# 03_CONNECTOR.net
KiCad netlist of a schematic drawn in Altium Designer
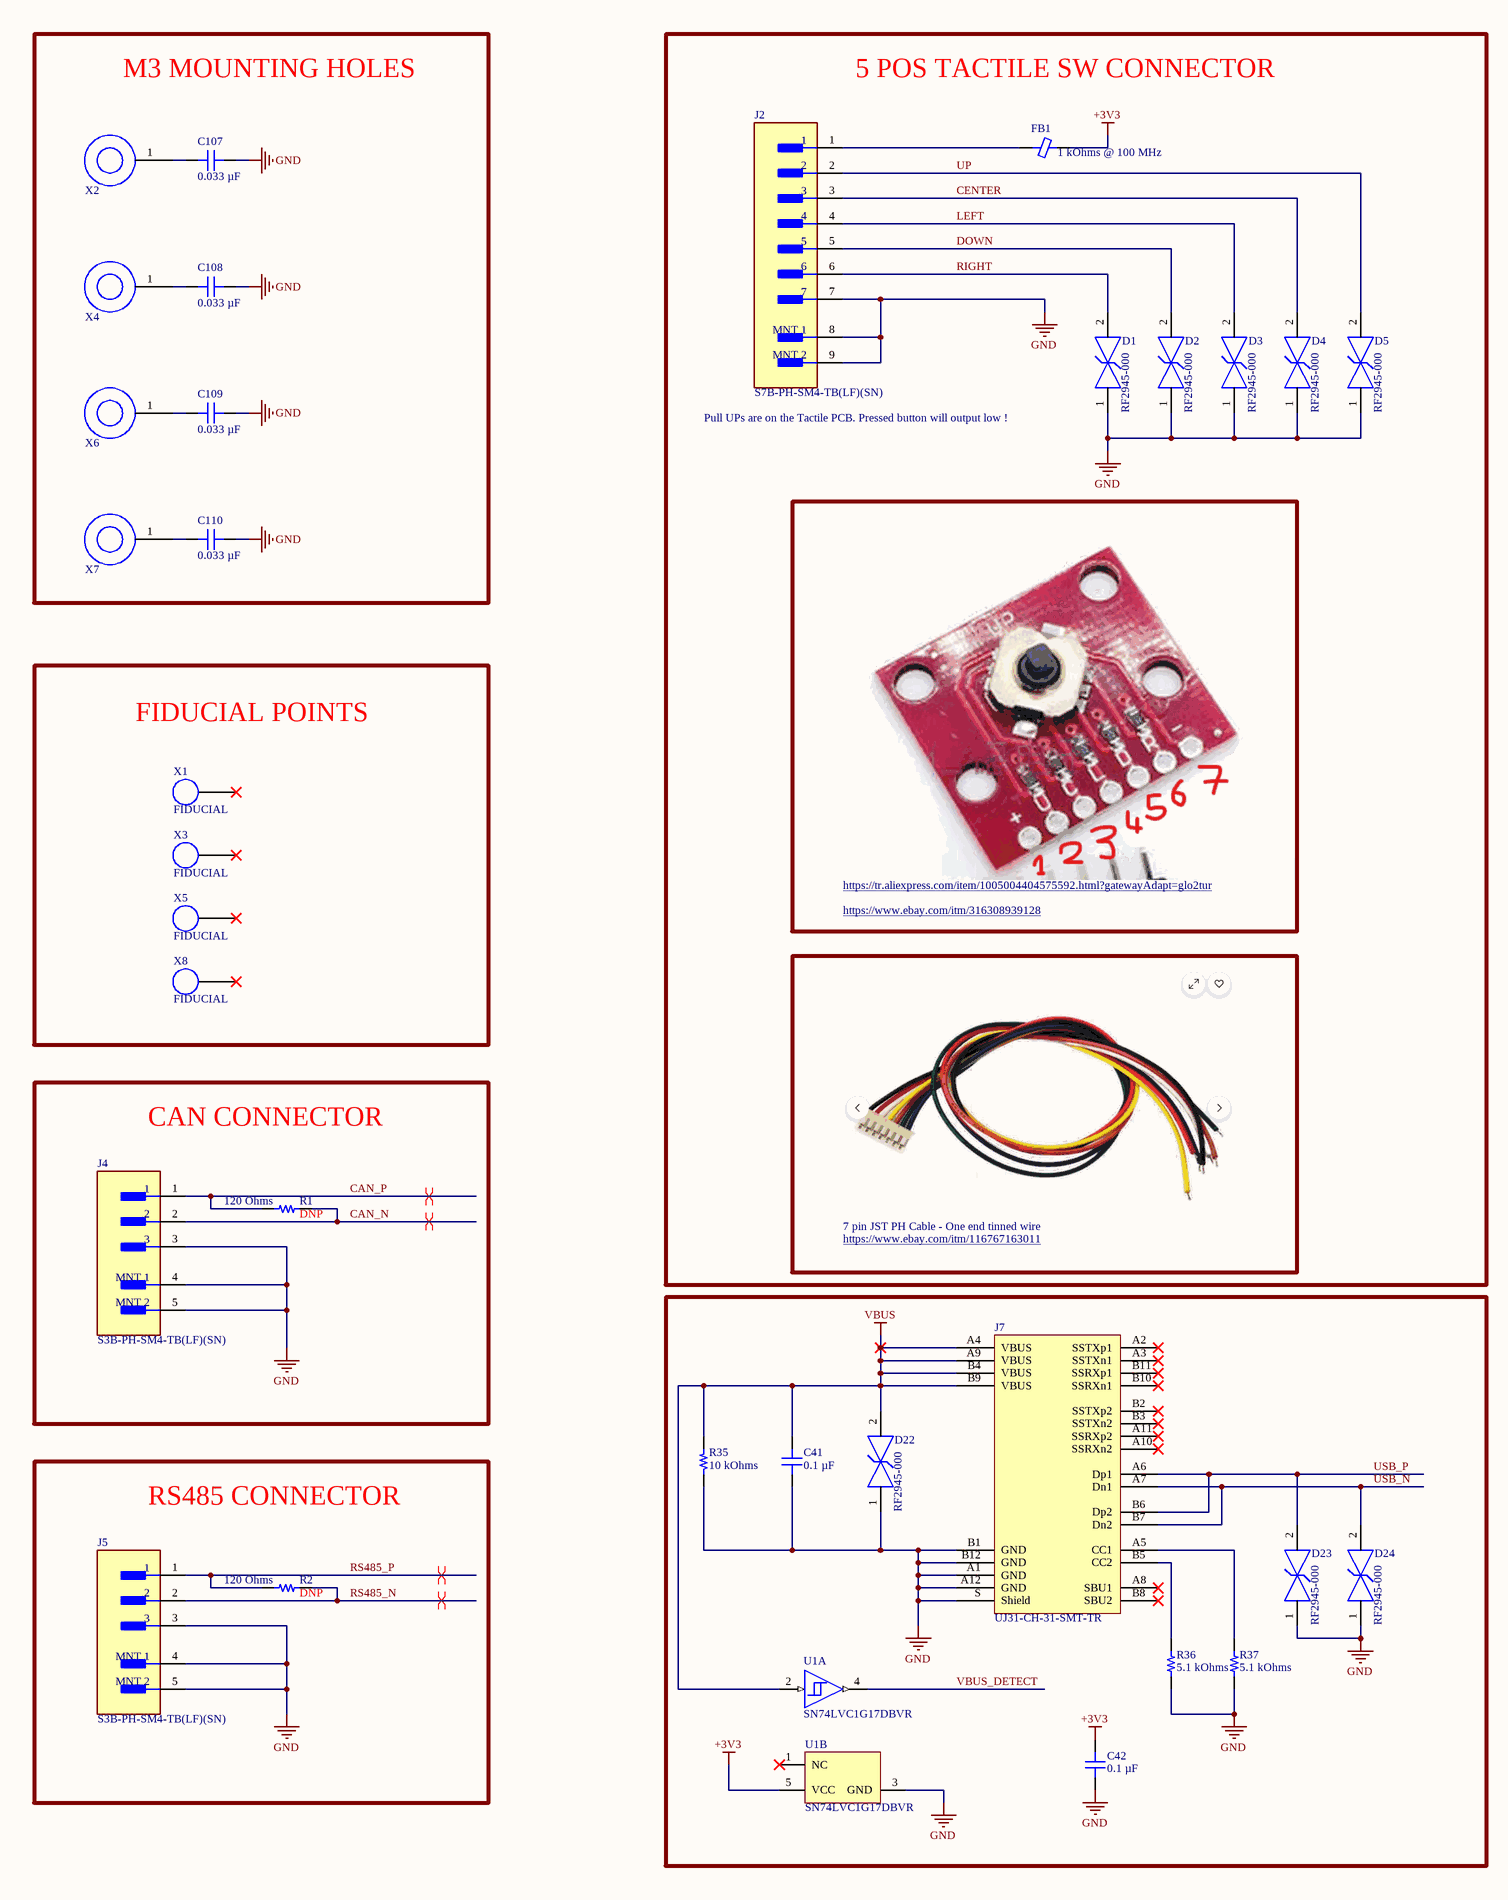
[diagram p0: 03_CONNECTOR.SchDoc, left]
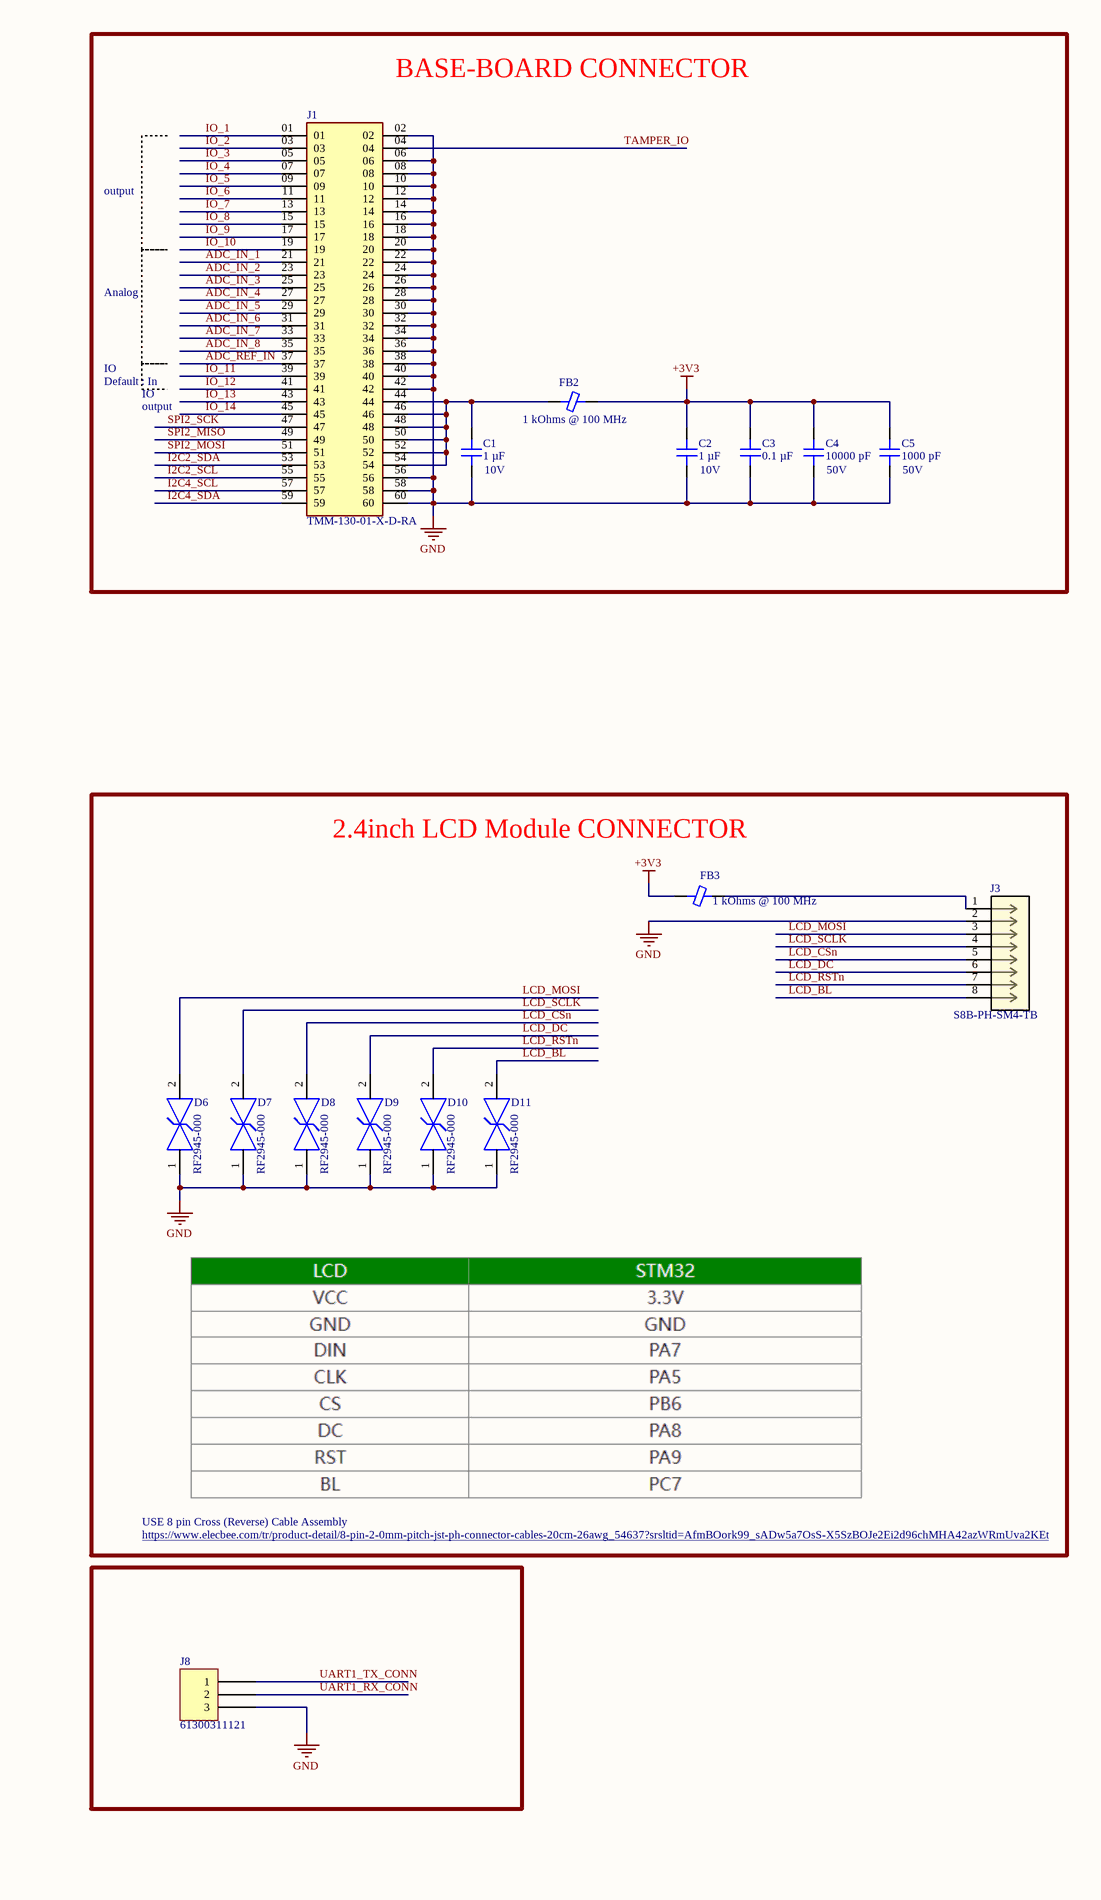
[diagram p1: 03_CONNECTOR.SchDoc, right]

(export (version "E")
  (design (tool "Eeschema 10.0.6"))
  (components
    (comp (ref "C1")
      (value "1 µF")
      (footprint "CAP 0402_1005")
      (description "CAP CER 1UF 10V X7S 0402")
      (fields
        (field (name "PART NUMBER") "C1005X7S1A105K050BC")
        (field (name "MANUFACTURER") "TDK Corporation")
        (field (name "VOLTAGE - RATED") "10V")
      )
      (libsource (lib "Celestial Altium Library - altium_library") (part "Capacitor"))
    )
    (comp (ref "C2")
      (value "1 µF")
      (footprint "CAP 0402_1005")
      (description "CAP CER 1UF 10V X7S 0402")
      (fields
        (field (name "PART NUMBER") "C1005X7S1A105K050BC")
        (field (name "MANUFACTURER") "TDK Corporation")
        (field (name "VOLTAGE - RATED") "10V")
      )
      (libsource (lib "Celestial Altium Library - altium_library") (part "Capacitor"))
    )
    (comp (ref "C3")
      (value "0.1 µF")
      (footprint "MURATA GRM155 0402_1005")
      (description "CAP CER 0.1UF 50V X7R 0402")
      (fields
        (field (name "PART NUMBER") "GRM155R71H104KE14J")
        (field (name "CAPACITANCE") "0.1 µF")
        (field (name "MANUFACTURER") "Murata Electronics")
      )
      (libsource (lib "Celestial Altium Library - altium_library") (part "Capacitor"))
    )
    (comp (ref "C4")
      (value "10000 pF")
      (footprint "CAP 0402_1005")
      (description "CAP CER 10000PF 50V X7R 0402")
      (fields
        (field (name "PART NUMBER") "CC0402KRX7R9BB103")
        (field (name "MANUFACTURER") "Yageo")
        (field (name "VOLTAGE - RATED") "50V")
      )
      (libsource (lib "Celestial Altium Library - altium_library") (part "Capacitor"))
    )
    (comp (ref "C5")
      (value "1000 pF")
      (footprint "CAP 0402_1005")
      (description "CAP CER 1000PF 50V X7R 0402")
      (fields
        (field (name "PART NUMBER") "CC0402KRX7R9BB102")
        (field (name "MANUFACTURER") "Yageo")
        (field (name "VOLTAGE - RATED") "50V")
      )
      (libsource (lib "Celestial Altium Library - altium_library") (part "Capacitor"))
    )
    (comp (ref "C41")
      (value "0.1 µF")
      (footprint "MURATA GRM155 0402_1005")
      (description "CAP CER 0.1UF 50V X7R 0402")
      (fields
        (field (name "PART NUMBER") "GRM155R71H104KE14J")
        (field (name "CAPACITANCE") "0.1 µF")
        (field (name "MANUFACTURER") "Murata Electronics")
      )
      (libsource (lib "Celestial Altium Library - altium_library") (part "Capacitor"))
    )
    (comp (ref "C42")
      (value "0.1 µF")
      (footprint "MURATA GRM155 0402_1005")
      (description "CAP CER 0.1UF 50V X7R 0402")
      (fields
        (field (name "PART NUMBER") "GRM155R71H104KE14J")
        (field (name "CAPACITANCE") "0.1 µF")
        (field (name "MANUFACTURER") "Murata Electronics")
      )
      (libsource (lib "Celestial Altium Library - altium_library") (part "Capacitor"))
    )
    (comp (ref "C107")
      (value "0.033 µF")
      (footprint "CAP 1210_3225 - 1MM")
      (description "CAP CER 0.033UF 1KV X7R 1210")
      (fields (field (name "PART NUMBER") "C1210X333KDRAC7800") (field (name "MANUFACTURER") "KEMET"))
      (libsource (lib "Celestial Altium Library - altium_library") (part "Capacitor"))
    )
    (comp (ref "C108")
      (value "0.033 µF")
      (footprint "CAP 1210_3225 - 1MM")
      (description "CAP CER 0.033UF 1KV X7R 1210")
      (fields (field (name "PART NUMBER") "C1210X333KDRAC7800") (field (name "MANUFACTURER") "KEMET"))
      (libsource (lib "Celestial Altium Library - altium_library") (part "Capacitor"))
    )
    (comp (ref "C109")
      (value "0.033 µF")
      (footprint "CAP 1210_3225 - 1MM")
      (description "CAP CER 0.033UF 1KV X7R 1210")
      (fields (field (name "PART NUMBER") "C1210X333KDRAC7800") (field (name "MANUFACTURER") "KEMET"))
      (libsource (lib "Celestial Altium Library - altium_library") (part "Capacitor"))
    )
    (comp (ref "C110")
      (value "0.033 µF")
      (footprint "CAP 1210_3225 - 1MM")
      (description "CAP CER 0.033UF 1KV X7R 1210")
      (fields (field (name "PART NUMBER") "C1210X333KDRAC7800") (field (name "MANUFACTURER") "KEMET"))
      (libsource (lib "Celestial Altium Library - altium_library") (part "Capacitor"))
    )
    (comp (ref "D1")
      (value "RF2945-000")
      (footprint "FP-SESD0402-MFG")
      (description "TVS DIODE 7V 10V 0402")
      (fields
        (field (name "OCTOPART") "https://octopart.com/rf2945-000-littelfuse-56516902")
        (field (name "MANUFACTURER") "Littelfuse")
      )
      (libsource (lib "Altium Content Vault") (part "876f4347bf90aa6f500f43e3cd03972"))
    )
    (comp (ref "D2")
      (value "RF2945-000")
      (footprint "FP-SESD0402-MFG")
      (description "TVS DIODE 7V 10V 0402")
      (fields
        (field (name "OCTOPART") "https://octopart.com/rf2945-000-littelfuse-56516902")
        (field (name "MANUFACTURER") "Littelfuse")
      )
      (libsource (lib "Altium Content Vault") (part "876f4347bf90aa6f500f43e3cd03972"))
    )
    (comp (ref "D3")
      (value "RF2945-000")
      (footprint "FP-SESD0402-MFG")
      (description "TVS DIODE 7V 10V 0402")
      (fields
        (field (name "OCTOPART") "https://octopart.com/rf2945-000-littelfuse-56516902")
        (field (name "MANUFACTURER") "Littelfuse")
      )
      (libsource (lib "Altium Content Vault") (part "876f4347bf90aa6f500f43e3cd03972"))
    )
    (comp (ref "D4")
      (value "RF2945-000")
      (footprint "FP-SESD0402-MFG")
      (description "TVS DIODE 7V 10V 0402")
      (fields
        (field (name "OCTOPART") "https://octopart.com/rf2945-000-littelfuse-56516902")
        (field (name "MANUFACTURER") "Littelfuse")
      )
      (libsource (lib "Altium Content Vault") (part "876f4347bf90aa6f500f43e3cd03972"))
    )
    (comp (ref "D5")
      (value "RF2945-000")
      (footprint "FP-SESD0402-MFG")
      (description "TVS DIODE 7V 10V 0402")
      (fields
        (field (name "OCTOPART") "https://octopart.com/rf2945-000-littelfuse-56516902")
        (field (name "MANUFACTURER") "Littelfuse")
      )
      (libsource (lib "Altium Content Vault") (part "876f4347bf90aa6f500f43e3cd03972"))
    )
    (comp (ref "D6")
      (value "RF2945-000")
      (footprint "FP-SESD0402-MFG")
      (description "TVS DIODE 7V 10V 0402")
      (fields
        (field (name "OCTOPART") "https://octopart.com/rf2945-000-littelfuse-56516902")
        (field (name "MANUFACTURER") "Littelfuse")
      )
      (libsource (lib "Altium Content Vault") (part "876f4347bf90aa6f500f43e3cd03972"))
    )
    (comp (ref "D7")
      (value "RF2945-000")
      (footprint "FP-SESD0402-MFG")
      (description "TVS DIODE 7V 10V 0402")
      (fields
        (field (name "OCTOPART") "https://octopart.com/rf2945-000-littelfuse-56516902")
        (field (name "MANUFACTURER") "Littelfuse")
      )
      (libsource (lib "Altium Content Vault") (part "876f4347bf90aa6f500f43e3cd03972"))
    )
    (comp (ref "D8")
      (value "RF2945-000")
      (footprint "FP-SESD0402-MFG")
      (description "TVS DIODE 7V 10V 0402")
      (fields
        (field (name "OCTOPART") "https://octopart.com/rf2945-000-littelfuse-56516902")
        (field (name "MANUFACTURER") "Littelfuse")
      )
      (libsource (lib "Altium Content Vault") (part "876f4347bf90aa6f500f43e3cd03972"))
    )
    (comp (ref "D9")
      (value "RF2945-000")
      (footprint "FP-SESD0402-MFG")
      (description "TVS DIODE 7V 10V 0402")
      (fields
        (field (name "OCTOPART") "https://octopart.com/rf2945-000-littelfuse-56516902")
        (field (name "MANUFACTURER") "Littelfuse")
      )
      (libsource (lib "Altium Content Vault") (part "876f4347bf90aa6f500f43e3cd03972"))
    )
    (comp (ref "D10")
      (value "RF2945-000")
      (footprint "FP-SESD0402-MFG")
      (description "TVS DIODE 7V 10V 0402")
      (fields
        (field (name "OCTOPART") "https://octopart.com/rf2945-000-littelfuse-56516902")
        (field (name "MANUFACTURER") "Littelfuse")
      )
      (libsource (lib "Altium Content Vault") (part "876f4347bf90aa6f500f43e3cd03972"))
    )
    (comp (ref "D11")
      (value "RF2945-000")
      (footprint "FP-SESD0402-MFG")
      (description "TVS DIODE 7V 10V 0402")
      (fields
        (field (name "OCTOPART") "https://octopart.com/rf2945-000-littelfuse-56516902")
        (field (name "MANUFACTURER") "Littelfuse")
      )
      (libsource (lib "Altium Content Vault") (part "876f4347bf90aa6f500f43e3cd03972"))
    )
    (comp (ref "D22")
      (value "RF2945-000")
      (footprint "FP-SESD0402-MFG")
      (description "TVS DIODE 7V 10V 0402")
      (fields
        (field (name "OCTOPART") "https://octopart.com/rf2945-000-littelfuse-56516902")
        (field (name "MANUFACTURER") "Littelfuse")
      )
      (libsource (lib "Altium Content Vault") (part "876f4347bf90aa6f500f43e3cd03972"))
    )
    (comp (ref "D23")
      (value "RF2945-000")
      (footprint "FP-SESD0402-MFG")
      (description "TVS DIODE 7V 10V 0402")
      (fields
        (field (name "OCTOPART") "https://octopart.com/rf2945-000-littelfuse-56516902")
        (field (name "MANUFACTURER") "Littelfuse")
      )
      (libsource (lib "Altium Content Vault") (part "876f4347bf90aa6f500f43e3cd03972"))
    )
    (comp (ref "D24")
      (value "RF2945-000")
      (footprint "FP-SESD0402-MFG")
      (description "TVS DIODE 7V 10V 0402")
      (fields
        (field (name "OCTOPART") "https://octopart.com/rf2945-000-littelfuse-56516902")
        (field (name "MANUFACTURER") "Littelfuse")
      )
      (libsource (lib "Altium Content Vault") (part "876f4347bf90aa6f500f43e3cd03972"))
    )
    (comp (ref "FB1")
      (value "1 kOhms @ 100 MHz")
      (footprint "FER 1206_3216")
      (description "FERRITE BEAD 1K OHM 1206 1LN")
      (fields
        (field (name "PART NUMBER") "BLM31KN102SN1L")
        (field (name "MANUFACTURER") "Murata Electronics")
      )
      (libsource (lib "Celestial Altium Library - altium_library") (part "Ferrite Chip"))
    )
    (comp (ref "FB2")
      (value "1 kOhms @ 100 MHz")
      (footprint "FER 1206_3216")
      (description "FERRITE BEAD 1K OHM 1206 1LN")
      (fields
        (field (name "PART NUMBER") "BLM31KN102SN1L")
        (field (name "MANUFACTURER") "Murata Electronics")
      )
      (libsource (lib "Celestial Altium Library - altium_library") (part "Ferrite Chip"))
    )
    (comp (ref "FB3")
      (value "1 kOhms @ 100 MHz")
      (footprint "FER 1206_3216")
      (description "FERRITE BEAD 1K OHM 1206 1LN")
      (fields
        (field (name "PART NUMBER") "BLM31KN102SN1L")
        (field (name "MANUFACTURER") "Murata Electronics")
      )
      (libsource (lib "Celestial Altium Library - altium_library") (part "Ferrite Chip"))
    )
    (comp (ref "J1")
      (value "TMM-130-01-X-D-RA")
      (footprint "SAMTEC_TMM-130-01-X-D-RA")
      (description "Connector Header Through Hole, Right Angle 60 position 0.079 (2.00mm)")
      (fields (field (name "MF") "Samtec") (field (name "MP") "TMM-130-01-L-D-RA"))
      (libsource (lib "TMM-130-01-X-D-RA") (part "TMM-130-01-X-D-RA"))
    )
    (comp (ref "J2")
      (value "S7B-PH-SM4-TB(LF)(SN)")
      (footprint "FP-S7B-PH-SM4-TB_LF_SN-MFG")
      (description "CONN HEADER SMD R/A 7POS 2MM")
      (libsource (lib "Altium Content Vault") (part "b0abd15a4b949e48c0a2e6945bb7dcd"))
    )
    (comp (ref "J3")
      (value "S8B-PH-SM4-TB")
      (footprint "CONN_S8B-PH-SM4-TB_JST")
      (description "Description")
      (fields (field (name "COPYRIGHT") "Copyright (C) 2025 Ultra Librarian. All rights reserved."))
      (libsource (lib "S8B-PH-SM4-TB") (part "S8B-PH-SM4-TB"))
    )
    (comp (ref "J4")
      (value "S3B-PH-SM4-TB(LF)(SN)")
      (footprint "FP-S3B-PH-SM4-TB_LF_SN-MFG")
      (description "CONN HEADER SMD R/A 3POS 2MM")
      (libsource (lib "Altium Content Vault") (part "38689d6f3df0f9b234c6ddcef280d85"))
    )
    (comp (ref "J5")
      (value "S3B-PH-SM4-TB(LF)(SN)")
      (footprint "FP-S3B-PH-SM4-TB_LF_SN-MFG")
      (description "CONN HEADER SMD R/A 3POS 2MM")
      (libsource (lib "Altium Content Vault") (part "38689d6f3df0f9b234c6ddcef280d85"))
    )
    (comp (ref "J7")
      (value "UJ31-CH-31-SMT-TR")
      (footprint "CUI UJ31-CH-31-SMT-TR")
      (description "CONN RCPT USB3.1 TYPEC 24POS R/A")
      (fields (field (name "MANUFACTURER") "CUI Devices"))
      (libsource (lib "Celestial Altium Library - altium_library") (part "USB 3.0 Type C"))
    )
    (comp (ref "J8")
      (value "61300311121")
      (footprint "WURTH WE-PHD 61300311121")
      (description "CONN HEADER VERT 3POS 2.54MM")
      (fields (field (name "MANUFACTURER") "Würth Elektronik"))
      (libsource (lib "Celestial Altium Library - altium_library") (part "3 Pin"))
    )
    (comp (ref "R1")
      (value "120 Ohms")
      (footprint "YAGEO RES 0805_2012")
      (description "RES 120 OHM 1% 1/8W 0805")
      (fields (field (name "PART NUMBER") "RC0805FR-07120RL") (field (name "MANUFACTURER") "Yageo"))
      (libsource (lib "Celestial Altium Library - altium_library") (part "Resistor"))
    )
    (comp (ref "R2")
      (value "120 Ohms")
      (footprint "YAGEO RES 0805_2012")
      (description "RES 120 OHM 1% 1/8W 0805")
      (fields (field (name "PART NUMBER") "RC0805FR-07120RL") (field (name "MANUFACTURER") "Yageo"))
      (libsource (lib "Celestial Altium Library - altium_library") (part "Resistor"))
    )
    (comp (ref "R35")
      (value "10 kOhms")
      (footprint "RES 0402_1005")
      (description "RES 10K OHM 1% 1/16W 0402")
      (fields (field (name "PART NUMBER") "RC0402FR-0710KL") (field (name "MANUFACTURER") "Yageo"))
      (libsource (lib "LASER_DIAGNOSTIC_BOARD") (part "Resistor"))
    )
    (comp (ref "R36")
      (value "5.1 kOhms")
      (footprint "YAGEO RES 0402_1005")
      (description "RES 5.1K OHM 1% 1/16W 0402")
      (fields (field (name "PART NUMBER") "RC0402FR-075K1L") (field (name "MANUFACTURER") "Yageo"))
      (libsource (lib "Celestial Altium Library - altium_library") (part "Resistor"))
    )
    (comp (ref "R37")
      (value "5.1 kOhms")
      (footprint "YAGEO RES 0402_1005")
      (description "RES 5.1K OHM 1% 1/16W 0402")
      (fields (field (name "PART NUMBER") "RC0402FR-075K1L") (field (name "MANUFACTURER") "Yageo"))
      (libsource (lib "Celestial Altium Library - altium_library") (part "Resistor"))
    )
    (comp (ref "U1")
      (value "SN74LVC1G17DBVR")
      (footprint "DBV0005A_L")
      (description "Single Schmitt-Trigger Buffer, DBV0005A, LARGE T&R")
      (fields
        (field (name "MANUFACTURER") "Texas Instruments")
        (field (name "GENERIC PART NUMBER") "SN74LVC1G17")
      )
      (libsource (lib "Altium Content Vault") (part "TI-SN74XXX1XXX-XX-5-SCHMITT"))
    )
    (comp (ref "X1")
      (value "FIDUCIAL")
      (footprint "FIDUCIAL")
      (description "FIDUCIAL 1mm")
      (libsource (lib "MISC_Library") (part "FIDUCIAL"))
    )
    (comp (ref "X2")
      (value "M3")
      (footprint "FIXING_M3")
      (description "FIXING HOLE M3")
      (libsource (lib "MISC_Library") (part "FIXING_M3"))
    )
    (comp (ref "X3")
      (value "FIDUCIAL")
      (footprint "FIDUCIAL")
      (description "FIDUCIAL 1mm")
      (libsource (lib "MISC_Library") (part "FIDUCIAL"))
    )
    (comp (ref "X4")
      (value "M3")
      (footprint "FIXING_M3")
      (description "FIXING HOLE M3")
      (libsource (lib "MISC_Library") (part "FIXING_M3"))
    )
    (comp (ref "X5")
      (value "FIDUCIAL")
      (footprint "FIDUCIAL")
      (description "FIDUCIAL 1mm")
      (libsource (lib "MISC_Library") (part "FIDUCIAL"))
    )
    (comp (ref "X6")
      (value "M3")
      (footprint "FIXING_M3")
      (description "FIXING HOLE M3")
      (libsource (lib "MISC_Library") (part "FIXING_M3"))
    )
    (comp (ref "X7")
      (value "M3")
      (footprint "FIXING_M3")
      (description "FIXING HOLE M3")
      (libsource (lib "MISC_Library") (part "FIXING_M3"))
    )
    (comp (ref "X8")
      (value "FIDUCIAL")
      (footprint "FIDUCIAL")
      (description "FIDUCIAL 1mm")
      (libsource (lib "MISC_Library") (part "FIDUCIAL"))
    )
  )
  (nets
    (net (code "1") (name "+3V3") (class "Default")
      (node (ref "C2") (pin "2") (pinfunction "2_2") (pintype "passive"))
      (node (ref "C3") (pin "2") (pinfunction "2_2") (pintype "passive"))
      (node (ref "C4") (pin "2") (pinfunction "2_2") (pintype "passive"))
      (node (ref "C42") (pin "2") (pinfunction "2_2") (pintype "passive"))
      (node (ref "C5") (pin "2") (pinfunction "2_2") (pintype "passive"))
      (node (ref "FB1") (pin "2") (pinfunction "2_2") (pintype "passive"))
      (node (ref "FB2") (pin "2") (pinfunction "2_2") (pintype "passive"))
      (node (ref "FB3") (pin "1") (pinfunction "1_1") (pintype "passive"))
      (node (ref "U1") (pin "5") (pinfunction "VCC_5") (pintype "power_in"))
    )
    (net (code "2") (name "/ADC_IN_1") (class "Default")
      (node (ref "J1") (pin "21") (pinfunction "21_21") (pintype "passive"))
    )
    (net (code "3") (name "/ADC_IN_2") (class "Default")
      (node (ref "J1") (pin "23") (pinfunction "23_23") (pintype "passive"))
    )
    (net (code "4") (name "/ADC_IN_3") (class "Default")
      (node (ref "J1") (pin "25") (pinfunction "25_25") (pintype "passive"))
    )
    (net (code "5") (name "/ADC_IN_4") (class "Default")
      (node (ref "J1") (pin "27") (pinfunction "27_27") (pintype "passive"))
    )
    (net (code "6") (name "/ADC_IN_5") (class "Default")
      (node (ref "J1") (pin "29") (pinfunction "29_29") (pintype "passive"))
    )
    (net (code "7") (name "/ADC_IN_6") (class "Default")
      (node (ref "J1") (pin "31") (pinfunction "31_31") (pintype "passive"))
    )
    (net (code "8") (name "/ADC_IN_7") (class "Default")
      (node (ref "J1") (pin "33") (pinfunction "33_33") (pintype "passive"))
    )
    (net (code "9") (name "/ADC_IN_8") (class "Default")
      (node (ref "J1") (pin "35") (pinfunction "35_35") (pintype "passive"))
    )
    (net (code "10") (name "/ADC_REF_IN") (class "Default")
      (node (ref "J1") (pin "37") (pinfunction "37_37") (pintype "passive"))
    )
    (net (code "11") (name "/CAN_N") (class "Default")
      (node (ref "J4") (pin "2") (pinfunction "2_2") (pintype "passive"))
      (node (ref "R1") (pin "2") (pinfunction "2_2") (pintype "passive"))
    )
    (net (code "12") (name "/CAN_P") (class "Default")
      (node (ref "J4") (pin "1") (pinfunction "1_1") (pintype "passive"))
      (node (ref "R1") (pin "1") (pinfunction "1_1") (pintype "passive"))
    )
    (net (code "13") (name "/CENTER") (class "Default")
      (node (ref "D4") (pin "2") (pinfunction "2_2") (pintype "passive"))
      (node (ref "J2") (pin "3") (pinfunction "3_3") (pintype "passive"))
    )
    (net (code "14") (name "/DOWN") (class "Default")
      (node (ref "D2") (pin "2") (pinfunction "2_2") (pintype "passive"))
      (node (ref "J2") (pin "5") (pinfunction "5_5") (pintype "passive"))
    )
    (net (code "15") (name "/I2C2_SCL") (class "Default")
      (node (ref "J1") (pin "55") (pinfunction "55_55") (pintype "passive"))
    )
    (net (code "16") (name "/I2C2_SDA") (class "Default")
      (node (ref "J1") (pin "53") (pinfunction "53_53") (pintype "passive"))
    )
    (net (code "17") (name "/I2C4_SCL") (class "Default")
      (node (ref "J1") (pin "57") (pinfunction "57_57") (pintype "passive"))
    )
    (net (code "18") (name "/I2C4_SDA") (class "Default")
      (node (ref "J1") (pin "59") (pinfunction "59_59") (pintype "passive"))
    )
    (net (code "19") (name "/IO_1") (class "Default")
      (node (ref "J1") (pin "01") (pinfunction "01_01") (pintype "passive"))
    )
    (net (code "20") (name "/IO_2") (class "Default")
      (node (ref "J1") (pin "03") (pinfunction "03_03") (pintype "passive"))
    )
    (net (code "21") (name "/IO_3") (class "Default")
      (node (ref "J1") (pin "05") (pinfunction "05_05") (pintype "passive"))
    )
    (net (code "22") (name "/IO_4") (class "Default")
      (node (ref "J1") (pin "07") (pinfunction "07_07") (pintype "passive"))
    )
    (net (code "23") (name "/IO_5") (class "Default")
      (node (ref "J1") (pin "09") (pinfunction "09_09") (pintype "passive"))
    )
    (net (code "24") (name "/IO_6") (class "Default")
      (node (ref "J1") (pin "11") (pinfunction "11_11") (pintype "passive"))
    )
    (net (code "25") (name "/IO_7") (class "Default")
      (node (ref "J1") (pin "13") (pinfunction "13_13") (pintype "passive"))
    )
    (net (code "26") (name "/IO_8") (class "Default")
      (node (ref "J1") (pin "15") (pinfunction "15_15") (pintype "passive"))
    )
    (net (code "27") (name "/IO_9") (class "Default")
      (node (ref "J1") (pin "17") (pinfunction "17_17") (pintype "passive"))
    )
    (net (code "28") (name "/IO_10") (class "Default")
      (node (ref "J1") (pin "19") (pinfunction "19_19") (pintype "passive"))
    )
    (net (code "29") (name "/IO_11") (class "Default")
      (node (ref "J1") (pin "39") (pinfunction "39_39") (pintype "passive"))
    )
    (net (code "30") (name "/IO_12") (class "Default")
      (node (ref "J1") (pin "41") (pinfunction "41_41") (pintype "passive"))
    )
    (net (code "31") (name "/IO_13") (class "Default")
      (node (ref "J1") (pin "43") (pinfunction "43_43") (pintype "passive"))
    )
    (net (code "32") (name "/IO_14") (class "Default")
      (node (ref "J1") (pin "45") (pinfunction "45_45") (pintype "passive"))
    )
    (net (code "33") (name "/LCD_BL") (class "Default")
      (node (ref "D11") (pin "2") (pinfunction "2_2") (pintype "passive"))
      (node (ref "J3") (pin "8") (pinfunction "8_8") (pintype "passive"))
    )
    (net (code "34") (name "/LCD_CSn") (class "Default")
      (node (ref "D8") (pin "2") (pinfunction "2_2") (pintype "passive"))
      (node (ref "J3") (pin "5") (pinfunction "5_5") (pintype "passive"))
    )
    (net (code "35") (name "/LCD_DC") (class "Default")
      (node (ref "D9") (pin "2") (pinfunction "2_2") (pintype "passive"))
      (node (ref "J3") (pin "6") (pinfunction "6_6") (pintype "passive"))
    )
    (net (code "36") (name "/LCD_MOSI") (class "Default")
      (node (ref "D6") (pin "2") (pinfunction "2_2") (pintype "passive"))
      (node (ref "J3") (pin "3") (pinfunction "3_3") (pintype "passive"))
    )
    (net (code "37") (name "/LCD_RSTn") (class "Default")
      (node (ref "D10") (pin "2") (pinfunction "2_2") (pintype "passive"))
      (node (ref "J3") (pin "7") (pinfunction "7_7") (pintype "passive"))
    )
    (net (code "38") (name "/LCD_SCLK") (class "Default")
      (node (ref "D7") (pin "2") (pinfunction "2_2") (pintype "passive"))
      (node (ref "J3") (pin "4") (pinfunction "4_4") (pintype "passive"))
    )
    (net (code "39") (name "/LEFT") (class "Default")
      (node (ref "D3") (pin "2") (pinfunction "2_2") (pintype "passive"))
      (node (ref "J2") (pin "4") (pinfunction "4_4") (pintype "passive"))
    )
    (net (code "40") (name "/RIGHT") (class "Default")
      (node (ref "D1") (pin "2") (pinfunction "2_2") (pintype "passive"))
      (node (ref "J2") (pin "6") (pinfunction "6_6") (pintype "passive"))
    )
    (net (code "41") (name "/RS485_N") (class "Default")
      (node (ref "J5") (pin "2") (pinfunction "2_2") (pintype "passive"))
      (node (ref "R2") (pin "2") (pinfunction "2_2") (pintype "passive"))
    )
    (net (code "42") (name "/RS485_P") (class "Default")
      (node (ref "J5") (pin "1") (pinfunction "1_1") (pintype "passive"))
      (node (ref "R2") (pin "1") (pinfunction "1_1") (pintype "passive"))
    )
    (net (code "43") (name "/SPI2_MISO") (class "Default")
      (node (ref "J1") (pin "49") (pinfunction "49_49") (pintype "passive"))
    )
    (net (code "44") (name "/SPI2_MOSI") (class "Default")
      (node (ref "J1") (pin "51") (pinfunction "51_51") (pintype "passive"))
    )
    (net (code "45") (name "/SPI2_SCK") (class "Default")
      (node (ref "J1") (pin "47") (pinfunction "47_47") (pintype "passive"))
    )
    (net (code "46") (name "/TAMPER_IO") (class "Default")
      (node (ref "J1") (pin "04") (pinfunction "04_04") (pintype "passive"))
    )
    (net (code "47") (name "/UART1_RX_CONN") (class "Default")
      (node (ref "J8") (pin "2") (pinfunction "2_2") (pintype "passive"))
    )
    (net (code "48") (name "/UART1_TX_CONN") (class "Default")
      (node (ref "J8") (pin "1") (pinfunction "1_1") (pintype "passive"))
    )
    (net (code "49") (name "/UP") (class "Default")
      (node (ref "D5") (pin "2") (pinfunction "2_2") (pintype "passive"))
      (node (ref "J2") (pin "2") (pinfunction "2_2") (pintype "passive"))
    )
    (net (code "50") (name "/USB_N") (class "Default")
      (node (ref "D24") (pin "2") (pinfunction "2_2") (pintype "passive"))
      (node (ref "J7") (pin "A7") (pinfunction "Dn1_A7") (pintype "passive"))
      (node (ref "J7") (pin "B7") (pinfunction "Dn2_B7") (pintype "passive"))
    )
    (net (code "51") (name "/USB_P") (class "Default")
      (node (ref "D23") (pin "2") (pinfunction "2_2") (pintype "passive"))
      (node (ref "J7") (pin "A6") (pinfunction "Dp1_A6") (pintype "passive"))
      (node (ref "J7") (pin "B6") (pinfunction "Dp2_B6") (pintype "passive"))
    )
    (net (code "52") (name "/VBUS_DETECT") (class "Default")
      (node (ref "U1") (pin "4") (pinfunction "Y_4") (pintype "output"))
    )
    (net (code "53") (name "GND") (class "Default")
      (node (ref "C1") (pin "1") (pinfunction "1_1") (pintype "passive"))
      (node (ref "C107") (pin "2") (pinfunction "2_2") (pintype "passive"))
      (node (ref "C108") (pin "2") (pinfunction "2_2") (pintype "passive"))
      (node (ref "C109") (pin "2") (pinfunction "2_2") (pintype "passive"))
      (node (ref "C110") (pin "2") (pinfunction "2_2") (pintype "passive"))
      (node (ref "C2") (pin "1") (pinfunction "1_1") (pintype "passive"))
      (node (ref "C3") (pin "1") (pinfunction "1_1") (pintype "passive"))
      (node (ref "C4") (pin "1") (pinfunction "1_1") (pintype "passive"))
      (node (ref "C41") (pin "1") (pinfunction "1_1") (pintype "passive"))
      (node (ref "C42") (pin "1") (pinfunction "1_1") (pintype "passive"))
      (node (ref "C5") (pin "1") (pinfunction "1_1") (pintype "passive"))
      (node (ref "D1") (pin "1") (pinfunction "1_1") (pintype "passive"))
      (node (ref "D10") (pin "1") (pinfunction "1_1") (pintype "passive"))
      (node (ref "D11") (pin "1") (pinfunction "1_1") (pintype "passive"))
      (node (ref "D2") (pin "1") (pinfunction "1_1") (pintype "passive"))
      (node (ref "D22") (pin "1") (pinfunction "1_1") (pintype "passive"))
      (node (ref "D23") (pin "1") (pinfunction "1_1") (pintype "passive"))
      (node (ref "D24") (pin "1") (pinfunction "1_1") (pintype "passive"))
      (node (ref "D3") (pin "1") (pinfunction "1_1") (pintype "passive"))
      (node (ref "D4") (pin "1") (pinfunction "1_1") (pintype "passive"))
      (node (ref "D5") (pin "1") (pinfunction "1_1") (pintype "passive"))
      (node (ref "D6") (pin "1") (pinfunction "1_1") (pintype "passive"))
      (node (ref "D7") (pin "1") (pinfunction "1_1") (pintype "passive"))
      (node (ref "D8") (pin "1") (pinfunction "1_1") (pintype "passive"))
      (node (ref "D9") (pin "1") (pinfunction "1_1") (pintype "passive"))
      (node (ref "J1") (pin "02") (pinfunction "02_02") (pintype "passive"))
      (node (ref "J1") (pin "06") (pinfunction "06_06") (pintype "passive"))
      (node (ref "J1") (pin "08") (pinfunction "08_08") (pintype "passive"))
      (node (ref "J1") (pin "10") (pinfunction "10_10") (pintype "passive"))
      (node (ref "J1") (pin "12") (pinfunction "12_12") (pintype "passive"))
      (node (ref "J1") (pin "14") (pinfunction "14_14") (pintype "passive"))
      (node (ref "J1") (pin "16") (pinfunction "16_16") (pintype "passive"))
      (node (ref "J1") (pin "18") (pinfunction "18_18") (pintype "passive"))
      (node (ref "J1") (pin "20") (pinfunction "20_20") (pintype "passive"))
      (node (ref "J1") (pin "22") (pinfunction "22_22") (pintype "passive"))
      (node (ref "J1") (pin "24") (pinfunction "24_24") (pintype "passive"))
      (node (ref "J1") (pin "26") (pinfunction "26_26") (pintype "passive"))
      (node (ref "J1") (pin "28") (pinfunction "28_28") (pintype "passive"))
      (node (ref "J1") (pin "30") (pinfunction "30_30") (pintype "passive"))
      (node (ref "J1") (pin "32") (pinfunction "32_32") (pintype "passive"))
      (node (ref "J1") (pin "34") (pinfunction "34_34") (pintype "passive"))
      (node (ref "J1") (pin "36") (pinfunction "36_36") (pintype "passive"))
      (node (ref "J1") (pin "38") (pinfunction "38_38") (pintype "passive"))
      (node (ref "J1") (pin "40") (pinfunction "40_40") (pintype "passive"))
      (node (ref "J1") (pin "42") (pinfunction "42_42") (pintype "passive"))
      (node (ref "J1") (pin "56") (pinfunction "56_56") (pintype "passive"))
      (node (ref "J1") (pin "58") (pinfunction "58_58") (pintype "passive"))
      (node (ref "J1") (pin "60") (pinfunction "60_60") (pintype "passive"))
      (node (ref "J2") (pin "7") (pinfunction "7_7") (pintype "passive"))
      (node (ref "J2") (pin "8") (pinfunction "MNT_1_8") (pintype "passive"))
      (node (ref "J2") (pin "9") (pinfunction "MNT_2_9") (pintype "passive"))
      (node (ref "J3") (pin "2") (pinfunction "2_2") (pintype "passive"))
      (node (ref "J4") (pin "3") (pinfunction "3_3") (pintype "passive"))
      (node (ref "J4") (pin "4") (pinfunction "MNT_1_4") (pintype "passive"))
      (node (ref "J4") (pin "5") (pinfunction "MNT_2_5") (pintype "passive"))
      (node (ref "J5") (pin "3") (pinfunction "3_3") (pintype "passive"))
      (node (ref "J5") (pin "4") (pinfunction "MNT_1_4") (pintype "passive"))
      (node (ref "J5") (pin "5") (pinfunction "MNT_2_5") (pintype "passive"))
      (node (ref "J7") (pin "A1") (pinfunction "GND_A1") (pintype "passive"))
      (node (ref "J7") (pin "A12") (pinfunction "GND_A12") (pintype "passive"))
      (node (ref "J7") (pin "B1") (pinfunction "GND_B1") (pintype "passive"))
      (node (ref "J7") (pin "B12") (pinfunction "GND_B12") (pintype "passive"))
      (node (ref "J7") (pin "S") (pinfunction "Shield_S") (pintype "passive"))
      (node (ref "J8") (pin "3") (pinfunction "3_3") (pintype "passive"))
      (node (ref "R35") (pin "2") (pinfunction "2_2") (pintype "passive"))
      (node (ref "R36") (pin "1") (pinfunction "1_1") (pintype "passive"))
      (node (ref "R37") (pin "1") (pinfunction "1_1") (pintype "passive"))
      (node (ref "U1") (pin "3") (pinfunction "GND_3") (pintype "power_in"))
    )
    (net (code "54") (name "Net-(C1-Pad2)") (class "Default")
      (node (ref "C1") (pin "2") (pinfunction "2_2") (pintype "passive"))
      (node (ref "FB2") (pin "1") (pinfunction "1_1") (pintype "passive"))
      (node (ref "J1") (pin "44") (pinfunction "44_44") (pintype "passive"))
      (node (ref "J1") (pin "46") (pinfunction "46_46") (pintype "passive"))
      (node (ref "J1") (pin "48") (pinfunction "48_48") (pintype "passive"))
      (node (ref "J1") (pin "50") (pinfunction "50_50") (pintype "passive"))
      (node (ref "J1") (pin "52") (pinfunction "52_52") (pintype "passive"))
      (node (ref "J1") (pin "54") (pinfunction "54_54") (pintype "passive"))
    )
    (net (code "55") (name "Net-(C107-Pad1)") (class "Default")
      (node (ref "C107") (pin "1") (pinfunction "1_1") (pintype "passive"))
      (node (ref "X2") (pin "1") (pinfunction "1_1") (pintype "passive"))
    )
    (net (code "56") (name "Net-(C108-Pad1)") (class "Default")
      (node (ref "C108") (pin "1") (pinfunction "1_1") (pintype "passive"))
      (node (ref "X4") (pin "1") (pinfunction "1_1") (pintype "passive"))
    )
    (net (code "57") (name "Net-(C109-Pad1)") (class "Default")
      (node (ref "C109") (pin "1") (pinfunction "1_1") (pintype "passive"))
      (node (ref "X6") (pin "1") (pinfunction "1_1") (pintype "passive"))
    )
    (net (code "58") (name "Net-(C110-Pad1)") (class "Default")
      (node (ref "C110") (pin "1") (pinfunction "1_1") (pintype "passive"))
      (node (ref "X7") (pin "1") (pinfunction "1_1") (pintype "passive"))
    )
    (net (code "59") (name "Net-(FB1-Pad1)") (class "Default")
      (node (ref "FB1") (pin "1") (pinfunction "1_1") (pintype "passive"))
      (node (ref "J2") (pin "1") (pinfunction "1_1") (pintype "passive"))
    )
    (net (code "60") (name "Net-(FB3-Pad2)") (class "Default")
      (node (ref "FB3") (pin "2") (pinfunction "2_2") (pintype "passive"))
      (node (ref "J3") (pin "1") (pinfunction "1_1") (pintype "passive"))
    )
    (net (code "61") (name "Net-(J7-CC1)") (class "Default")
      (node (ref "J7") (pin "A5") (pinfunction "CC1_A5") (pintype "passive"))
      (node (ref "R37") (pin "2") (pinfunction "2_2") (pintype "passive"))
    )
    (net (code "62") (name "Net-(J7-CC2)") (class "Default")
      (node (ref "J7") (pin "B5") (pinfunction "CC2_B5") (pintype "passive"))
      (node (ref "R36") (pin "2") (pinfunction "2_2") (pintype "passive"))
    )
    (net (code "63") (name "VBUS") (class "Default")
      (node (ref "C41") (pin "2") (pinfunction "2_2") (pintype "passive"))
      (node (ref "D22") (pin "2") (pinfunction "2_2") (pintype "passive"))
      (node (ref "J7") (pin "A4") (pinfunction "VBUS_A4") (pintype "passive"))
      (node (ref "J7") (pin "A9") (pinfunction "VBUS_A9") (pintype "passive"))
      (node (ref "J7") (pin "B4") (pinfunction "VBUS_B4") (pintype "passive"))
      (node (ref "J7") (pin "B9") (pinfunction "VBUS_B9") (pintype "passive"))
      (node (ref "R35") (pin "1") (pinfunction "1_1") (pintype "passive"))
      (node (ref "U1") (pin "2") (pinfunction "A_2") (pintype "input"))
    )
    (net (code "64") (name "unconnected-(J7-SBU1-PadA8)") (class "Default")
      (node (ref "J7") (pin "A8") (pinfunction "SBU1_A8") (pintype "passive+no_connect"))
    )
    (net (code "65") (name "unconnected-(J7-SBU2-PadB8)") (class "Default")
      (node (ref "J7") (pin "B8") (pinfunction "SBU2_B8") (pintype "passive+no_connect"))
    )
    (net (code "66") (name "unconnected-(J7-SSRXn1-PadB10)") (class "Default")
      (node (ref "J7") (pin "B10") (pinfunction "SSRXn1_B10") (pintype "passive+no_connect"))
    )
    (net (code "67") (name "unconnected-(J7-SSRXn2-PadA10)") (class "Default")
      (node (ref "J7") (pin "A10") (pinfunction "SSRXn2_A10") (pintype "passive+no_connect"))
    )
    (net (code "68") (name "unconnected-(J7-SSRXp1-PadB11)") (class "Default")
      (node (ref "J7") (pin "B11") (pinfunction "SSRXp1_B11") (pintype "passive+no_connect"))
    )
    (net (code "69") (name "unconnected-(J7-SSRXp2-PadA11)") (class "Default")
      (node (ref "J7") (pin "A11") (pinfunction "SSRXp2_A11") (pintype "passive+no_connect"))
    )
    (net (code "70") (name "unconnected-(J7-SSTXn1-PadA3)") (class "Default")
      (node (ref "J7") (pin "A3") (pinfunction "SSTXn1_A3") (pintype "passive+no_connect"))
    )
    (net (code "71") (name "unconnected-(J7-SSTXn2-PadB3)") (class "Default")
      (node (ref "J7") (pin "B3") (pinfunction "SSTXn2_B3") (pintype "passive+no_connect"))
    )
    (net (code "72") (name "unconnected-(J7-SSTXp1-PadA2)") (class "Default")
      (node (ref "J7") (pin "A2") (pinfunction "SSTXp1_A2") (pintype "passive+no_connect"))
    )
    (net (code "73") (name "unconnected-(J7-SSTXp2-PadB2)") (class "Default")
      (node (ref "J7") (pin "B2") (pinfunction "SSTXp2_B2") (pintype "passive+no_connect"))
    )
    (net (code "74") (name "unconnected-(U1B-NC-Pad1)") (class "Default")
      (node (ref "U1") (pin "1") (pinfunction "NC_1") (pintype "passive+no_connect"))
    )
    (net (code "75") (name "unconnected-(X1-Pad1)") (class "Default")
      (node (ref "X1") (pin "1") (pinfunction "1_1") (pintype "passive+no_connect"))
    )
    (net (code "76") (name "unconnected-(X3-Pad1)") (class "Default")
      (node (ref "X3") (pin "1") (pinfunction "1_1") (pintype "passive+no_connect"))
    )
    (net (code "77") (name "unconnected-(X5-Pad1)") (class "Default")
      (node (ref "X5") (pin "1") (pinfunction "1_1") (pintype "passive+no_connect"))
    )
    (net (code "78") (name "unconnected-(X8-Pad1)") (class "Default")
      (node (ref "X8") (pin "1") (pinfunction "1_1") (pintype "passive+no_connect"))
    )
  )
)
